# SRAM_256Kx32_TSOP44_2.net
KiCad netlist of a schematic drawn in Altium Designer
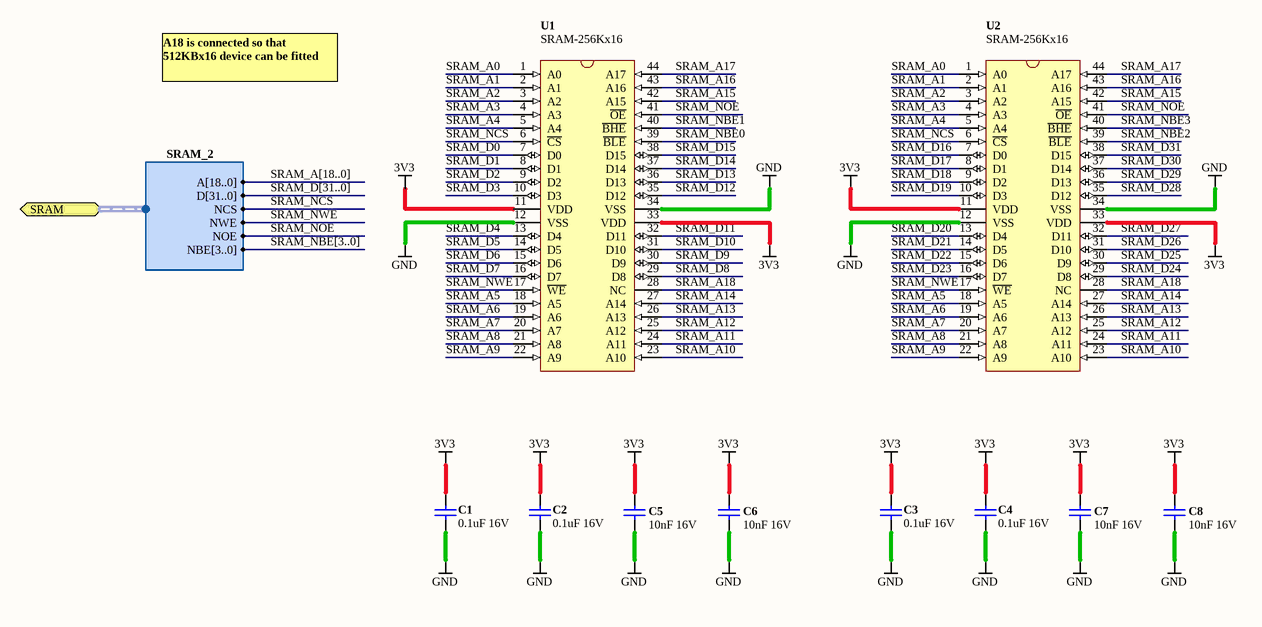
[diagram p0: SRAM_256Kx32_TSOP44_2.SchDoc]

(export (version "E")
  (design (tool "Eeschema 10.0.6"))
  (components
    (comp (ref "C1")
      (value "0.1uF 16V")
      (footprint "CAPC1005-STAR")
      (description "Capacitor, Ceramic, 0.1uF 10% 16V 0402 (1005) X7R")
      (fields (field (name "TOLERANCE") "10 %"))
      (libsource (lib "altium-import") (part "root_0_mirrored_CAP-NP_"))
    )
    (comp (ref "C2")
      (value "0.1uF 16V")
      (footprint "CAPC1005-STAR")
      (description "Capacitor, Ceramic, 0.1uF 10% 16V 0402 (1005) X7R")
      (fields (field (name "TOLERANCE") "10 %"))
      (libsource (lib "altium-import") (part "root_0_mirrored_CAP-NP_"))
    )
    (comp (ref "C3")
      (value "0.1uF 16V")
      (footprint "CAPC1005-STAR")
      (description "Capacitor, Ceramic, 0.1uF 10% 16V 0402 (1005) X7R")
      (fields (field (name "TOLERANCE") "10 %"))
      (libsource (lib "altium-import") (part "root_0_mirrored_CAP-NP_"))
    )
    (comp (ref "C4")
      (value "0.1uF 16V")
      (footprint "CAPC1005-STAR")
      (description "Capacitor, Ceramic, 0.1uF 10% 16V 0402 (1005) X7R")
      (fields (field (name "TOLERANCE") "10 %"))
      (libsource (lib "altium-import") (part "root_0_mirrored_CAP-NP_"))
    )
    (comp (ref "C5")
      (value "10nF 16V")
      (footprint "CAPC1005-STAR")
      (description "Capacitor, Ceramic, 10nF 10% 16V 0402 (1005) X7R")
      (fields (field (name "TOLERANCE") "10 %"))
      (libsource (lib "altium-import") (part "root_0_CAP-NP_"))
    )
    (comp (ref "C6")
      (value "10nF 16V")
      (footprint "CAPC1005-STAR")
      (description "Capacitor, Ceramic, 10nF 10% 16V 0402 (1005) X7R")
      (fields (field (name "TOLERANCE") "10 %"))
      (libsource (lib "altium-import") (part "root_0_CAP-NP_"))
    )
    (comp (ref "C7")
      (value "10nF 16V")
      (footprint "CAPC1005-STAR")
      (description "Capacitor, Ceramic, 10nF 10% 16V 0402 (1005) X7R")
      (fields (field (name "TOLERANCE") "10 %"))
      (libsource (lib "altium-import") (part "root_0_CAP-NP_"))
    )
    (comp (ref "C8")
      (value "10nF 16V")
      (footprint "CAPC1005-STAR")
      (description "Capacitor, Ceramic, 10nF 10% 16V 0402 (1005) X7R")
      (fields (field (name "TOLERANCE") "10 %"))
      (libsource (lib "altium-import") (part "root_0_CAP-NP_"))
    )
    (comp (ref "U1")
      (value "SRAM-256Kx16")
      (footprint "TSOP80P1176-44")
      (description "K6R4016V1D-TC10T, 256K x 16-Bit SRAM, TSOP44")
      (libsource (lib "altium-import") (part "root_0_K6R4016V1D-T_"))
    )
    (comp (ref "U2")
      (value "SRAM-256Kx16")
      (footprint "TSOP80P1176-44")
      (description "K6R4016V1D-TC10T, 256K x 16-Bit SRAM, TSOP44")
      (libsource (lib "altium-import") (part "root_0_K6R4016V1D-T_"))
    )
  )
  (nets
    (net (code "2") (name "/SRAM_A0") (class "Default")
      (node (ref "U1") (pin "1") (pinfunction "A0_1") (pintype "input"))
      (node (ref "U2") (pin "1") (pinfunction "A0_1") (pintype "input"))
    )
    (net (code "3") (name "/SRAM_A1") (class "Default")
      (node (ref "U1") (pin "2") (pinfunction "A1_2") (pintype "input"))
      (node (ref "U2") (pin "2") (pinfunction "A1_2") (pintype "input"))
    )
    (net (code "4") (name "/SRAM_A2") (class "Default")
      (node (ref "U1") (pin "3") (pinfunction "A2_3") (pintype "input"))
      (node (ref "U2") (pin "3") (pinfunction "A2_3") (pintype "input"))
    )
    (net (code "5") (name "/SRAM_A3") (class "Default")
      (node (ref "U1") (pin "4") (pinfunction "A3_4") (pintype "input"))
      (node (ref "U2") (pin "4") (pinfunction "A3_4") (pintype "input"))
    )
    (net (code "6") (name "/SRAM_A4") (class "Default")
      (node (ref "U1") (pin "5") (pinfunction "A4_5") (pintype "input"))
      (node (ref "U2") (pin "5") (pinfunction "A4_5") (pintype "input"))
    )
    (net (code "7") (name "/SRAM_A5") (class "Default")
      (node (ref "U1") (pin "18") (pinfunction "A5_18") (pintype "input"))
      (node (ref "U2") (pin "18") (pinfunction "A5_18") (pintype "input"))
    )
    (net (code "8") (name "/SRAM_A6") (class "Default")
      (node (ref "U1") (pin "19") (pinfunction "A6_19") (pintype "input"))
      (node (ref "U2") (pin "19") (pinfunction "A6_19") (pintype "input"))
    )
    (net (code "9") (name "/SRAM_A7") (class "Default")
      (node (ref "U1") (pin "20") (pinfunction "A7_20") (pintype "input"))
      (node (ref "U2") (pin "20") (pinfunction "A7_20") (pintype "input"))
    )
    (net (code "10") (name "/SRAM_A8") (class "Default")
      (node (ref "U1") (pin "21") (pinfunction "A8_21") (pintype "input"))
      (node (ref "U2") (pin "21") (pinfunction "A8_21") (pintype "input"))
    )
    (net (code "11") (name "/SRAM_A9") (class "Default")
      (node (ref "U1") (pin "22") (pinfunction "A9_22") (pintype "input"))
      (node (ref "U2") (pin "22") (pinfunction "A9_22") (pintype "input"))
    )
    (net (code "12") (name "/SRAM_A10") (class "Default")
      (node (ref "U1") (pin "23") (pinfunction "A10_23") (pintype "input"))
      (node (ref "U2") (pin "23") (pinfunction "A10_23") (pintype "input"))
    )
    (net (code "13") (name "/SRAM_A11") (class "Default")
      (node (ref "U1") (pin "24") (pinfunction "A11_24") (pintype "input"))
      (node (ref "U2") (pin "24") (pinfunction "A11_24") (pintype "input"))
    )
    (net (code "14") (name "/SRAM_A12") (class "Default")
      (node (ref "U1") (pin "25") (pinfunction "A12_25") (pintype "input"))
      (node (ref "U2") (pin "25") (pinfunction "A12_25") (pintype "input"))
    )
    (net (code "15") (name "/SRAM_A13") (class "Default")
      (node (ref "U1") (pin "26") (pinfunction "A13_26") (pintype "input"))
      (node (ref "U2") (pin "26") (pinfunction "A13_26") (pintype "input"))
    )
    (net (code "16") (name "/SRAM_A14") (class "Default")
      (node (ref "U1") (pin "27") (pinfunction "A14_27") (pintype "input"))
      (node (ref "U2") (pin "27") (pinfunction "A14_27") (pintype "input"))
    )
    (net (code "17") (name "/SRAM_A15") (class "Default")
      (node (ref "U1") (pin "42") (pinfunction "A15_42") (pintype "input"))
      (node (ref "U2") (pin "42") (pinfunction "A15_42") (pintype "input"))
    )
    (net (code "18") (name "/SRAM_A16") (class "Default")
      (node (ref "U1") (pin "43") (pinfunction "A16_43") (pintype "input"))
      (node (ref "U2") (pin "43") (pinfunction "A16_43") (pintype "input"))
    )
    (net (code "19") (name "/SRAM_A17") (class "Default")
      (node (ref "U1") (pin "44") (pinfunction "A17_44") (pintype "input"))
      (node (ref "U2") (pin "44") (pinfunction "A17_44") (pintype "input"))
    )
    (net (code "20") (name "/SRAM_A18") (class "Default")
      (node (ref "U1") (pin "28") (pinfunction "NC_28") (pintype "passive"))
      (node (ref "U2") (pin "28") (pinfunction "NC_28") (pintype "passive"))
    )
    (net (code "22") (name "/SRAM_D0") (class "Default")
      (node (ref "U1") (pin "7") (pinfunction "D0_7") (pintype "bidirectional"))
    )
    (net (code "23") (name "/SRAM_D1") (class "Default")
      (node (ref "U1") (pin "8") (pinfunction "D1_8") (pintype "bidirectional"))
    )
    (net (code "24") (name "/SRAM_D2") (class "Default")
      (node (ref "U1") (pin "9") (pinfunction "D2_9") (pintype "bidirectional"))
    )
    (net (code "25") (name "/SRAM_D3") (class "Default")
      (node (ref "U1") (pin "10") (pinfunction "D3_10") (pintype "bidirectional"))
    )
    (net (code "26") (name "/SRAM_D4") (class "Default")
      (node (ref "U1") (pin "13") (pinfunction "D4_13") (pintype "bidirectional"))
    )
    (net (code "27") (name "/SRAM_D5") (class "Default")
      (node (ref "U1") (pin "14") (pinfunction "D5_14") (pintype "bidirectional"))
    )
    (net (code "28") (name "/SRAM_D6") (class "Default")
      (node (ref "U1") (pin "15") (pinfunction "D6_15") (pintype "bidirectional"))
    )
    (net (code "29") (name "/SRAM_D7") (class "Default")
      (node (ref "U1") (pin "16") (pinfunction "D7_16") (pintype "bidirectional"))
    )
    (net (code "30") (name "/SRAM_D8") (class "Default")
      (node (ref "U1") (pin "29") (pinfunction "D8_29") (pintype "bidirectional"))
    )
    (net (code "31") (name "/SRAM_D9") (class "Default")
      (node (ref "U1") (pin "30") (pinfunction "D9_30") (pintype "bidirectional"))
    )
    (net (code "32") (name "/SRAM_D10") (class "Default")
      (node (ref "U1") (pin "31") (pinfunction "D10_31") (pintype "bidirectional"))
    )
    (net (code "33") (name "/SRAM_D11") (class "Default")
      (node (ref "U1") (pin "32") (pinfunction "D11_32") (pintype "bidirectional"))
    )
    (net (code "34") (name "/SRAM_D12") (class "Default")
      (node (ref "U1") (pin "35") (pinfunction "D12_35") (pintype "bidirectional"))
    )
    (net (code "35") (name "/SRAM_D13") (class "Default")
      (node (ref "U1") (pin "36") (pinfunction "D13_36") (pintype "bidirectional"))
    )
    (net (code "36") (name "/SRAM_D14") (class "Default")
      (node (ref "U1") (pin "37") (pinfunction "D14_37") (pintype "bidirectional"))
    )
    (net (code "37") (name "/SRAM_D15") (class "Default")
      (node (ref "U1") (pin "38") (pinfunction "D15_38") (pintype "bidirectional"))
    )
    (net (code "38") (name "/SRAM_D16") (class "Default")
      (node (ref "U2") (pin "7") (pinfunction "D0_7") (pintype "bidirectional"))
    )
    (net (code "39") (name "/SRAM_D17") (class "Default")
      (node (ref "U2") (pin "8") (pinfunction "D1_8") (pintype "bidirectional"))
    )
    (net (code "40") (name "/SRAM_D18") (class "Default")
      (node (ref "U2") (pin "9") (pinfunction "D2_9") (pintype "bidirectional"))
    )
    (net (code "41") (name "/SRAM_D19") (class "Default")
      (node (ref "U2") (pin "10") (pinfunction "D3_10") (pintype "bidirectional"))
    )
    (net (code "42") (name "/SRAM_D20") (class "Default")
      (node (ref "U2") (pin "13") (pinfunction "D4_13") (pintype "bidirectional"))
    )
    (net (code "43") (name "/SRAM_D21") (class "Default")
      (node (ref "U2") (pin "14") (pinfunction "D5_14") (pintype "bidirectional"))
    )
    (net (code "44") (name "/SRAM_D22") (class "Default")
      (node (ref "U2") (pin "15") (pinfunction "D6_15") (pintype "bidirectional"))
    )
    (net (code "45") (name "/SRAM_D23") (class "Default")
      (node (ref "U2") (pin "16") (pinfunction "D7_16") (pintype "bidirectional"))
    )
    (net (code "46") (name "/SRAM_D24") (class "Default")
      (node (ref "U2") (pin "29") (pinfunction "D8_29") (pintype "bidirectional"))
    )
    (net (code "47") (name "/SRAM_D25") (class "Default")
      (node (ref "U2") (pin "30") (pinfunction "D9_30") (pintype "bidirectional"))
    )
    (net (code "48") (name "/SRAM_D26") (class "Default")
      (node (ref "U2") (pin "31") (pinfunction "D10_31") (pintype "bidirectional"))
    )
    (net (code "49") (name "/SRAM_D27") (class "Default")
      (node (ref "U2") (pin "32") (pinfunction "D11_32") (pintype "bidirectional"))
    )
    (net (code "50") (name "/SRAM_D28") (class "Default")
      (node (ref "U2") (pin "35") (pinfunction "D12_35") (pintype "bidirectional"))
    )
    (net (code "51") (name "/SRAM_D29") (class "Default")
      (node (ref "U2") (pin "36") (pinfunction "D13_36") (pintype "bidirectional"))
    )
    (net (code "52") (name "/SRAM_D30") (class "Default")
      (node (ref "U2") (pin "37") (pinfunction "D14_37") (pintype "bidirectional"))
    )
    (net (code "53") (name "/SRAM_D31") (class "Default")
      (node (ref "U2") (pin "38") (pinfunction "D15_38") (pintype "bidirectional"))
    )
    (net (code "55") (name "/SRAM_NBE0") (class "Default")
      (node (ref "U1") (pin "39") (pinfunction "~{BLE}_39") (pintype "input"))
    )
    (net (code "56") (name "/SRAM_NBE1") (class "Default")
      (node (ref "U1") (pin "40") (pinfunction "~{BHE}_40") (pintype "input"))
    )
    (net (code "57") (name "/SRAM_NBE2") (class "Default")
      (node (ref "U2") (pin "39") (pinfunction "~{BLE}_39") (pintype "input"))
    )
    (net (code "58") (name "/SRAM_NBE3") (class "Default")
      (node (ref "U2") (pin "40") (pinfunction "~{BHE}_40") (pintype "input"))
    )
    (net (code "59") (name "/SRAM_NCS") (class "Default")
      (node (ref "U1") (pin "6") (pinfunction "~{CS}_6") (pintype "input"))
      (node (ref "U2") (pin "6") (pinfunction "~{CS}_6") (pintype "input"))
    )
    (net (code "60") (name "/SRAM_NOE") (class "Default")
      (node (ref "U1") (pin "41") (pinfunction "~{OE}_41") (pintype "input"))
      (node (ref "U2") (pin "41") (pinfunction "~{OE}_41") (pintype "input"))
    )
    (net (code "61") (name "/SRAM_NWE") (class "Default")
      (node (ref "U1") (pin "17") (pinfunction "~{WE}_17") (pintype "input"))
      (node (ref "U2") (pin "17") (pinfunction "~{WE}_17") (pintype "input"))
    )
    (net (code "64") (name "3V3") (class "Default")
      (node (ref "C1") (pin "1") (pinfunction "1_1") (pintype "passive"))
      (node (ref "C2") (pin "1") (pinfunction "1_1") (pintype "passive"))
      (node (ref "C3") (pin "1") (pinfunction "1_1") (pintype "passive"))
      (node (ref "C4") (pin "1") (pinfunction "1_1") (pintype "passive"))
      (node (ref "C5") (pin "1") (pinfunction "1_1") (pintype "passive"))
      (node (ref "C6") (pin "1") (pinfunction "1_1") (pintype "passive"))
      (node (ref "C7") (pin "1") (pinfunction "1_1") (pintype "passive"))
      (node (ref "C8") (pin "1") (pinfunction "1_1") (pintype "passive"))
      (node (ref "U1") (pin "11") (pinfunction "VDD_11") (pintype "power_in"))
      (node (ref "U1") (pin "33") (pinfunction "VDD_33") (pintype "power_in"))
      (node (ref "U2") (pin "11") (pinfunction "VDD_11") (pintype "power_in"))
      (node (ref "U2") (pin "33") (pinfunction "VDD_33") (pintype "power_in"))
    )
    (net (code "65") (name "GND") (class "Default")
      (node (ref "C1") (pin "2") (pinfunction "2_2") (pintype "passive"))
      (node (ref "C2") (pin "2") (pinfunction "2_2") (pintype "passive"))
      (node (ref "C3") (pin "2") (pinfunction "2_2") (pintype "passive"))
      (node (ref "C4") (pin "2") (pinfunction "2_2") (pintype "passive"))
      (node (ref "C5") (pin "2") (pinfunction "2_2") (pintype "passive"))
      (node (ref "C6") (pin "2") (pinfunction "2_2") (pintype "passive"))
      (node (ref "C7") (pin "2") (pinfunction "2_2") (pintype "passive"))
      (node (ref "C8") (pin "2") (pinfunction "2_2") (pintype "passive"))
      (node (ref "U1") (pin "12") (pinfunction "VSS_12") (pintype "power_in"))
      (node (ref "U1") (pin "34") (pinfunction "VSS_34") (pintype "power_in"))
      (node (ref "U2") (pin "12") (pinfunction "VSS_12") (pintype "power_in"))
      (node (ref "U2") (pin "34") (pinfunction "VSS_34") (pintype "power_in"))
    )
  )
)
